# CCM_0012.net
KiCad netlist of a schematic drawn in EAGLE
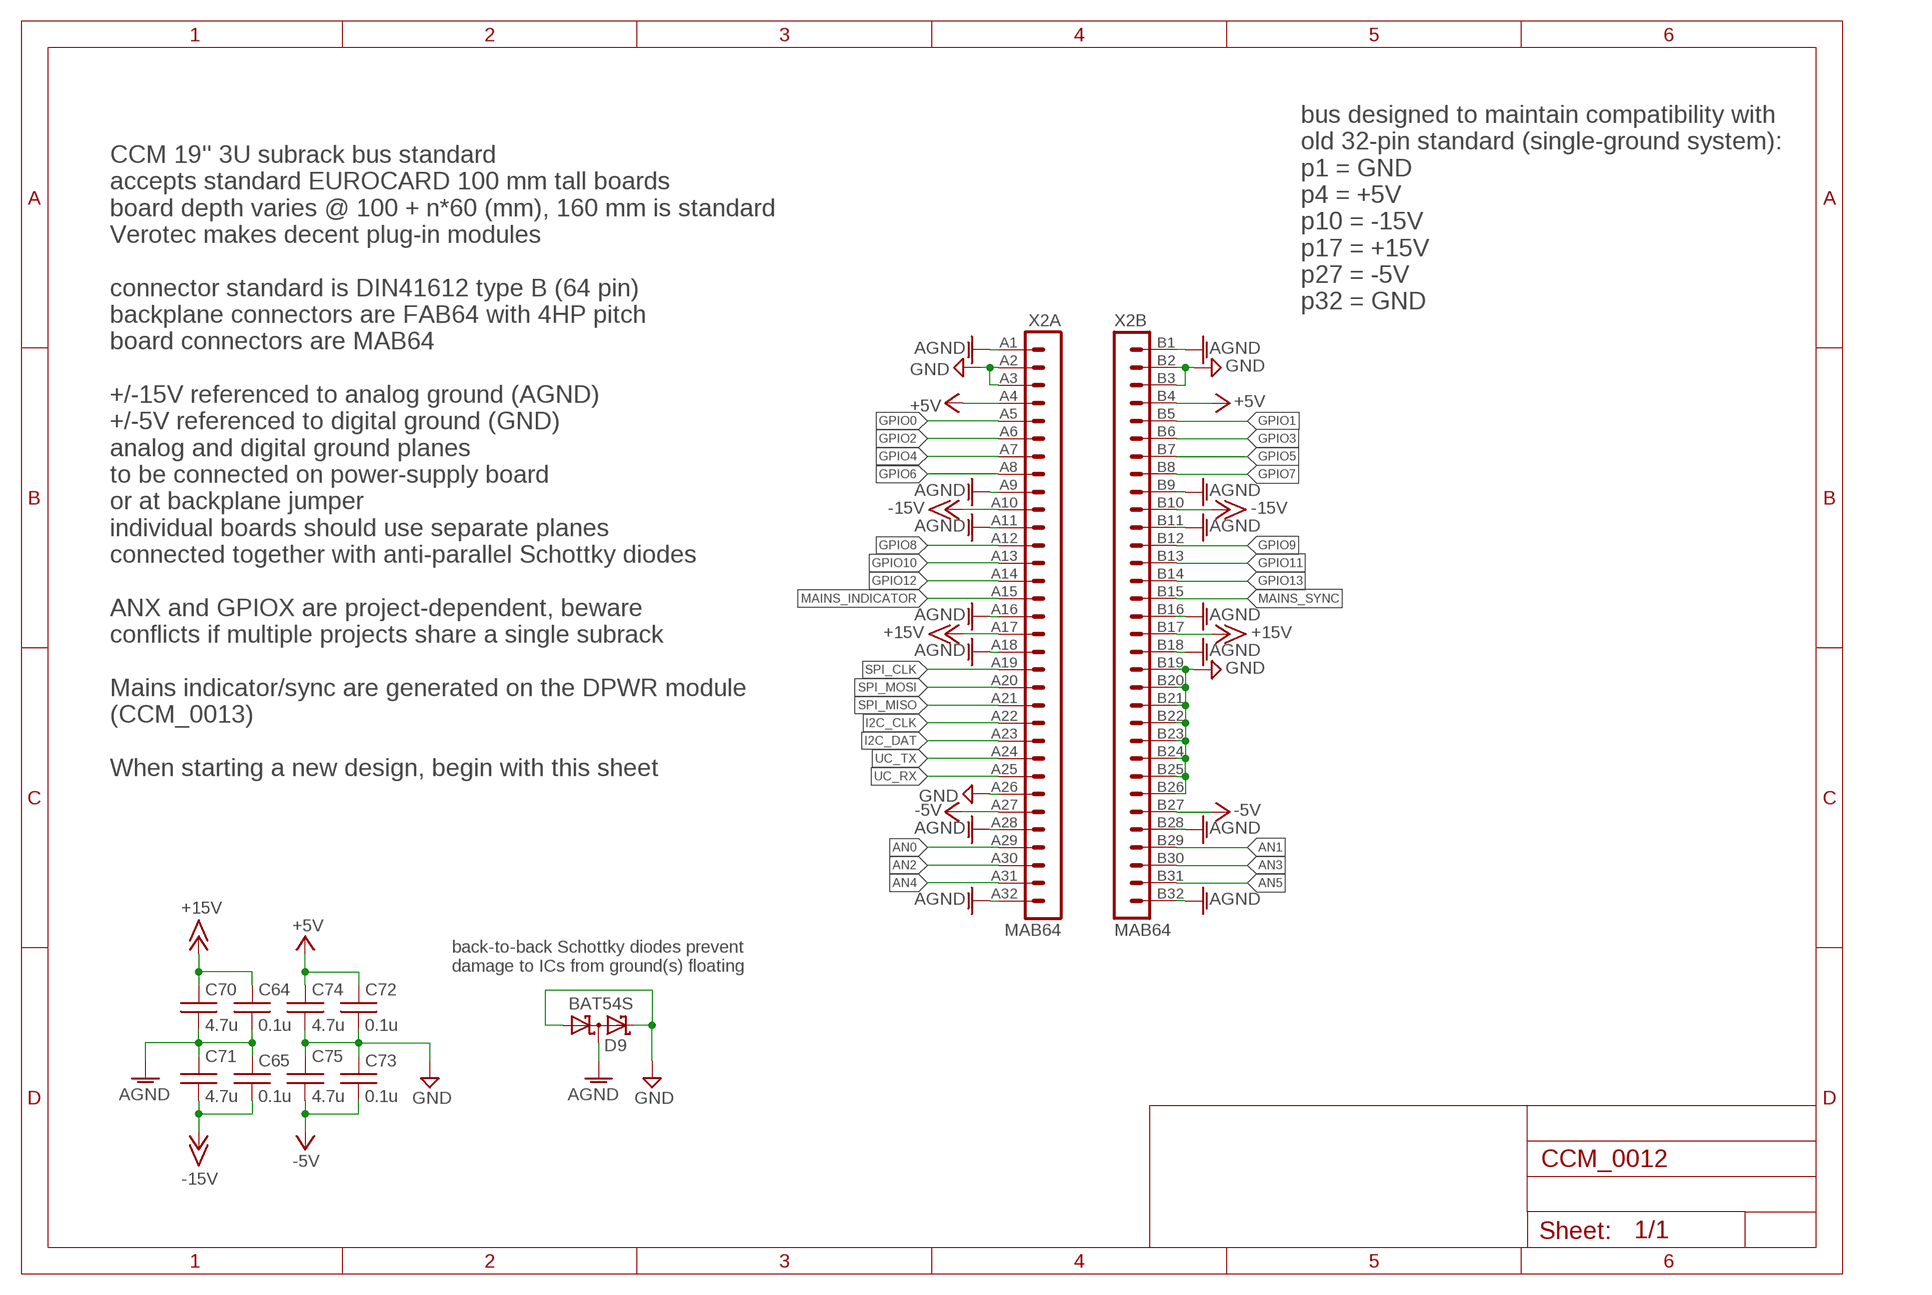
[diagram p0: schematic, sheet 1]

(export (version "E")
  (design (tool "Eeschema 10.0.6"))
  (components
    (comp (ref "C64")
      (value "0.1u")
      (footprint "eagle-import:0603")
      (libsource (lib "eagle-import") (part "C0603"))
    )
    (comp (ref "C65")
      (value "0.1u")
      (footprint "eagle-import:0603")
      (libsource (lib "eagle-import") (part "C0603"))
    )
    (comp (ref "C70")
      (value "4.7u")
      (footprint "eagle-import:0603")
      (libsource (lib "eagle-import") (part "C0603"))
    )
    (comp (ref "C71")
      (value "4.7u")
      (footprint "eagle-import:0603")
      (libsource (lib "eagle-import") (part "C0603"))
    )
    (comp (ref "C72")
      (value "0.1u")
      (footprint "eagle-import:0603")
      (libsource (lib "eagle-import") (part "C0603"))
    )
    (comp (ref "C73")
      (value "0.1u")
      (footprint "eagle-import:0603")
      (libsource (lib "eagle-import") (part "C0603"))
    )
    (comp (ref "C74")
      (value "4.7u")
      (footprint "eagle-import:0603")
      (libsource (lib "eagle-import") (part "C0603"))
    )
    (comp (ref "C75")
      (value "4.7u")
      (footprint "eagle-import:0603")
      (libsource (lib "eagle-import") (part "C0603"))
    )
    (comp (ref "D9")
      (value "BAT54S")
      (footprint "eagle-import:SOT23")
      (libsource (lib "eagle-import") (part "BAT54S"))
    )
    (comp (ref "X2")
      (value "MAB64")
      (footprint "eagle-import:MAB64")
      (libsource (lib "eagle-import") (part "MAB64"))
    )
  )
  (nets
    (net (code "1") (name "+5V") (class "Default")
      (node (ref "C72") (pin "1") (pinfunction "1_1") (pintype "passive"))
      (node (ref "C74") (pin "1") (pinfunction "1_1") (pintype "passive"))
      (node (ref "X2") (pin "A4") (pinfunction "4_A4") (pintype "passive"))
      (node (ref "X2") (pin "B4") (pinfunction "4_B4") (pintype "passive"))
    )
    (net (code "2") (name "+15V") (class "Default")
      (node (ref "C64") (pin "1") (pinfunction "1_1") (pintype "passive"))
      (node (ref "C70") (pin "1") (pinfunction "1_1") (pintype "passive"))
      (node (ref "X2") (pin "A17") (pinfunction "17_A17") (pintype "passive"))
      (node (ref "X2") (pin "B17") (pinfunction "17_B17") (pintype "passive"))
    )
    (net (code "3") (name "-5V") (class "Default")
      (node (ref "C73") (pin "2") (pinfunction "2_2") (pintype "passive"))
      (node (ref "C75") (pin "2") (pinfunction "2_2") (pintype "passive"))
      (node (ref "X2") (pin "A27") (pinfunction "27_A27") (pintype "passive"))
      (node (ref "X2") (pin "B27") (pinfunction "27_B27") (pintype "passive"))
    )
    (net (code "4") (name "-15V") (class "Default")
      (node (ref "C65") (pin "2") (pinfunction "2_2") (pintype "passive"))
      (node (ref "C71") (pin "2") (pinfunction "2_2") (pintype "passive"))
      (node (ref "X2") (pin "A10") (pinfunction "10_A10") (pintype "passive"))
      (node (ref "X2") (pin "B10") (pinfunction "10_B10") (pintype "passive"))
    )
    (net (code "5") (name "AGND") (class "Default")
      (node (ref "C64") (pin "2") (pinfunction "2_2") (pintype "passive"))
      (node (ref "C65") (pin "1") (pinfunction "1_1") (pintype "passive"))
      (node (ref "C70") (pin "2") (pinfunction "2_2") (pintype "passive"))
      (node (ref "C71") (pin "1") (pinfunction "1_1") (pintype "passive"))
      (node (ref "D9") (pin "3") (pinfunction "C1A2_3") (pintype "passive"))
      (node (ref "X2") (pin "A1") (pinfunction "1_A1") (pintype "passive"))
      (node (ref "X2") (pin "A11") (pinfunction "11_A11") (pintype "passive"))
      (node (ref "X2") (pin "A16") (pinfunction "16_A16") (pintype "passive"))
      (node (ref "X2") (pin "A18") (pinfunction "18_A18") (pintype "passive"))
      (node (ref "X2") (pin "A28") (pinfunction "28_A28") (pintype "passive"))
      (node (ref "X2") (pin "A32") (pinfunction "32_A32") (pintype "passive"))
      (node (ref "X2") (pin "A9") (pinfunction "9_A9") (pintype "passive"))
      (node (ref "X2") (pin "B1") (pinfunction "1_B1") (pintype "passive"))
      (node (ref "X2") (pin "B11") (pinfunction "11_B11") (pintype "passive"))
      (node (ref "X2") (pin "B16") (pinfunction "16_B16") (pintype "passive"))
      (node (ref "X2") (pin "B18") (pinfunction "18_B18") (pintype "passive"))
      (node (ref "X2") (pin "B28") (pinfunction "28_B28") (pintype "passive"))
      (node (ref "X2") (pin "B32") (pinfunction "32_B32") (pintype "passive"))
      (node (ref "X2") (pin "B9") (pinfunction "9_B9") (pintype "passive"))
    )
    (net (code "6") (name "AN0") (class "Default")
      (node (ref "X2") (pin "A29") (pinfunction "29_A29") (pintype "passive"))
    )
    (net (code "7") (name "AN1") (class "Default")
      (node (ref "X2") (pin "B29") (pinfunction "29_B29") (pintype "passive"))
    )
    (net (code "8") (name "AN2") (class "Default")
      (node (ref "X2") (pin "A30") (pinfunction "30_A30") (pintype "passive"))
    )
    (net (code "9") (name "AN3") (class "Default")
      (node (ref "X2") (pin "B30") (pinfunction "30_B30") (pintype "passive"))
    )
    (net (code "10") (name "AN4") (class "Default")
      (node (ref "X2") (pin "A31") (pinfunction "31_A31") (pintype "passive"))
    )
    (net (code "11") (name "AN5") (class "Default")
      (node (ref "X2") (pin "B31") (pinfunction "31_B31") (pintype "passive"))
    )
    (net (code "12") (name "GND") (class "Default")
      (node (ref "C72") (pin "2") (pinfunction "2_2") (pintype "passive"))
      (node (ref "C73") (pin "1") (pinfunction "1_1") (pintype "passive"))
      (node (ref "C74") (pin "2") (pinfunction "2_2") (pintype "passive"))
      (node (ref "C75") (pin "1") (pinfunction "1_1") (pintype "passive"))
      (node (ref "D9") (pin "1") (pinfunction "A1_1") (pintype "passive"))
      (node (ref "D9") (pin "2") (pinfunction "C2_2") (pintype "passive"))
      (node (ref "X2") (pin "A2") (pinfunction "2_A2") (pintype "passive"))
      (node (ref "X2") (pin "A26") (pinfunction "26_A26") (pintype "passive"))
      (node (ref "X2") (pin "A3") (pinfunction "3_A3") (pintype "passive"))
      (node (ref "X2") (pin "B19") (pinfunction "19_B19") (pintype "passive"))
      (node (ref "X2") (pin "B2") (pinfunction "2_B2") (pintype "passive"))
      (node (ref "X2") (pin "B20") (pinfunction "20_B20") (pintype "passive"))
      (node (ref "X2") (pin "B21") (pinfunction "21_B21") (pintype "passive"))
      (node (ref "X2") (pin "B22") (pinfunction "22_B22") (pintype "passive"))
      (node (ref "X2") (pin "B23") (pinfunction "23_B23") (pintype "passive"))
      (node (ref "X2") (pin "B24") (pinfunction "24_B24") (pintype "passive"))
      (node (ref "X2") (pin "B25") (pinfunction "25_B25") (pintype "passive"))
      (node (ref "X2") (pin "B26") (pinfunction "26_B26") (pintype "passive"))
      (node (ref "X2") (pin "B3") (pinfunction "3_B3") (pintype "passive"))
    )
    (net (code "13") (name "GPIO0") (class "Default")
      (node (ref "X2") (pin "A5") (pinfunction "5_A5") (pintype "passive"))
    )
    (net (code "14") (name "GPIO1") (class "Default")
      (node (ref "X2") (pin "B5") (pinfunction "5_B5") (pintype "passive"))
    )
    (net (code "15") (name "GPIO2") (class "Default")
      (node (ref "X2") (pin "A6") (pinfunction "6_A6") (pintype "passive"))
    )
    (net (code "16") (name "GPIO3") (class "Default")
      (node (ref "X2") (pin "B6") (pinfunction "6_B6") (pintype "passive"))
    )
    (net (code "17") (name "GPIO4") (class "Default")
      (node (ref "X2") (pin "A7") (pinfunction "7_A7") (pintype "passive"))
    )
    (net (code "18") (name "GPIO5") (class "Default")
      (node (ref "X2") (pin "B7") (pinfunction "7_B7") (pintype "passive"))
    )
    (net (code "19") (name "GPIO6") (class "Default")
      (node (ref "X2") (pin "A8") (pinfunction "8_A8") (pintype "passive"))
    )
    (net (code "20") (name "GPIO7") (class "Default")
      (node (ref "X2") (pin "B8") (pinfunction "8_B8") (pintype "passive"))
    )
    (net (code "21") (name "GPIO8") (class "Default")
      (node (ref "X2") (pin "A12") (pinfunction "12_A12") (pintype "passive"))
    )
    (net (code "22") (name "GPIO9") (class "Default")
      (node (ref "X2") (pin "B12") (pinfunction "12_B12") (pintype "passive"))
    )
    (net (code "23") (name "GPIO10") (class "Default")
      (node (ref "X2") (pin "A13") (pinfunction "13_A13") (pintype "passive"))
    )
    (net (code "24") (name "GPIO11") (class "Default")
      (node (ref "X2") (pin "B13") (pinfunction "13_B13") (pintype "passive"))
    )
    (net (code "25") (name "GPIO12") (class "Default")
      (node (ref "X2") (pin "A14") (pinfunction "14_A14") (pintype "passive"))
    )
    (net (code "26") (name "GPIO13") (class "Default")
      (node (ref "X2") (pin "B14") (pinfunction "14_B14") (pintype "passive"))
    )
    (net (code "27") (name "I2C_CLK") (class "Default")
      (node (ref "X2") (pin "A22") (pinfunction "22_A22") (pintype "passive"))
    )
    (net (code "28") (name "I2C_DAT") (class "Default")
      (node (ref "X2") (pin "A23") (pinfunction "23_A23") (pintype "passive"))
    )
    (net (code "29") (name "MAINS_INDICATOR") (class "Default")
      (node (ref "X2") (pin "A15") (pinfunction "15_A15") (pintype "passive"))
    )
    (net (code "30") (name "MAINS_SYNC") (class "Default")
      (node (ref "X2") (pin "B15") (pinfunction "15_B15") (pintype "passive"))
    )
    (net (code "31") (name "SPI_CLK") (class "Default")
      (node (ref "X2") (pin "A19") (pinfunction "19_A19") (pintype "passive"))
    )
    (net (code "32") (name "SPI_MISO") (class "Default")
      (node (ref "X2") (pin "A21") (pinfunction "21_A21") (pintype "passive"))
    )
    (net (code "33") (name "SPI_MOSI") (class "Default")
      (node (ref "X2") (pin "A20") (pinfunction "20_A20") (pintype "passive"))
    )
    (net (code "34") (name "UC_RX") (class "Default")
      (node (ref "X2") (pin "A25") (pinfunction "25_A25") (pintype "passive"))
    )
    (net (code "35") (name "UC_TX") (class "Default")
      (node (ref "X2") (pin "A24") (pinfunction "24_A24") (pintype "passive"))
    )
  )
)
